# LCD_Cape.net
KiCad netlist of a schematic drawn in Altium Designer
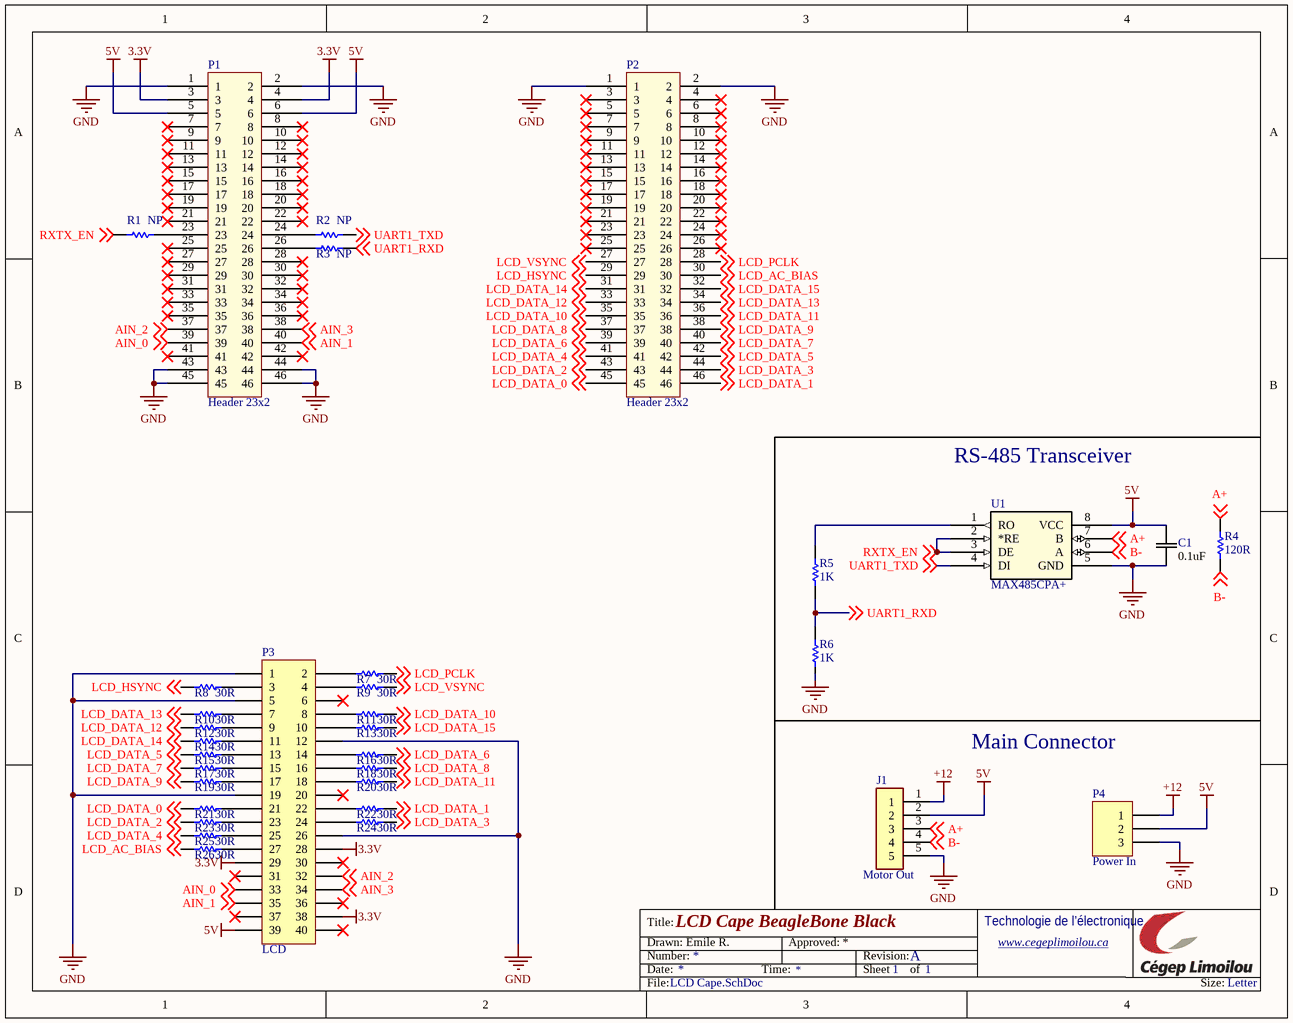
[diagram p0: LCD Cape.SchDoc]

(export (version "E")
  (design (tool "Eeschema 10.0.6"))
  (components
    (comp (ref "C1")
      (value "0.1uF")
      (footprint "0603")
      (description "Capacitor SMD 1206")
      (fields
        (field (name "MANUFACTURER_PART_NUMBER") "12065A820JAT2A")
        (field (name "Comment") "Capacitor 1206")
        (field (name "COPYRIGHT") "Copyright (C) 2018 Accelerated Designs. All rights reserved")
      )
      (libsource (lib "Schematic_Emile") (part "Capacitor 1206"))
    )
    (comp (ref "J1")
      (value "Motor Out")
      (footprint "JST 5POS 2.5mm 90°")
      (description "Connector")
      (fields (field (name "MANUFACTURER_PART_NUMBER") "S5B-XH-A-1(LF)(SN)"))
      (libsource (lib "Schematic_Emile") (part "JST 5POS"))
    )
    (comp (ref "P1") (value "Header 23x2") (libsource (lib "Schematic_Emile") (part "Header 23x2")))
    (comp (ref "P2") (value "Header 23x2") (libsource (lib "Schematic_Emile") (part "Header 23x2")))
    (comp (ref "P3")
      (value "LCD")
      (footprint "HDR2X20")
      (description "Header, 20-Pin, Dual row")
      (fields (field (name "PUBLISHER") "Altium Limited"))
      (libsource (lib "Miscellaneous Connectors") (part "Header 20X2"))
    )
    (comp (ref "P4")
      (value "Power In")
      (footprint "HDR1X3")
      (description "Header, 3-Pin")
      (fields (field (name "PUBLISHER") "Altium Limited"))
      (libsource (lib "Miscellaneous Connectors") (part "Header 3"))
    )
    (comp (ref "R1")
      (value "NP")
      (footprint "AXIAL-0.3")
      (description "Resistor")
      (fields (field (name "Comment") "Res1") (field (name "PUBLISHER") "Altium Limited"))
      (libsource (lib "Miscellaneous Devices") (part "Res1"))
    )
    (comp (ref "R2")
      (value "NP")
      (footprint "AXIAL-0.3")
      (description "Resistor")
      (fields (field (name "Comment") "Res1") (field (name "PUBLISHER") "Altium Limited"))
      (libsource (lib "Miscellaneous Devices") (part "Res1"))
    )
    (comp (ref "R3")
      (value "NP")
      (footprint "AXIAL-0.3")
      (description "Resistor")
      (fields (field (name "Comment") "Res1") (field (name "PUBLISHER") "Altium Limited"))
      (libsource (lib "Miscellaneous Devices") (part "Res1"))
    )
    (comp (ref "R4")
      (value "120R")
      (footprint "C1206")
      (description "Resistor")
      (fields (field (name "Comment") "Res1") (field (name "PUBLISHER") "Altium Limited"))
      (libsource (lib "Miscellaneous Devices") (part "Res1"))
    )
    (comp (ref "R5")
      (value "1K")
      (footprint "C1206")
      (description "Resistor")
      (fields (field (name "Comment") "Res1") (field (name "PUBLISHER") "Altium Limited"))
      (libsource (lib "Miscellaneous Devices") (part "Res1"))
    )
    (comp (ref "R6")
      (value "1K")
      (footprint "C1206")
      (description "Resistor")
      (fields (field (name "Comment") "Res1") (field (name "PUBLISHER") "Altium Limited"))
      (libsource (lib "Miscellaneous Devices") (part "Res1"))
    )
    (comp (ref "R7")
      (value "30R")
      (footprint "C1206")
      (description "Resistor")
      (fields (field (name "Comment") "Res1") (field (name "PUBLISHER") "Altium Limited"))
      (libsource (lib "Miscellaneous Devices") (part "Res1"))
    )
    (comp (ref "R8")
      (value "30R")
      (footprint "C1206")
      (description "Resistor")
      (fields (field (name "Comment") "Res1") (field (name "PUBLISHER") "Altium Limited"))
      (libsource (lib "Miscellaneous Devices") (part "Res1"))
    )
    (comp (ref "R9")
      (value "30R")
      (footprint "C1206")
      (description "Resistor")
      (fields (field (name "Comment") "Res1") (field (name "PUBLISHER") "Altium Limited"))
      (libsource (lib "Miscellaneous Devices") (part "Res1"))
    )
    (comp (ref "R10")
      (value "30R")
      (footprint "C1206")
      (description "Resistor")
      (fields (field (name "Comment") "Res1") (field (name "PUBLISHER") "Altium Limited"))
      (libsource (lib "Miscellaneous Devices") (part "Res1"))
    )
    (comp (ref "R11")
      (value "30R")
      (footprint "C1206")
      (description "Resistor")
      (fields (field (name "Comment") "Res1") (field (name "PUBLISHER") "Altium Limited"))
      (libsource (lib "Miscellaneous Devices") (part "Res1"))
    )
    (comp (ref "R12")
      (value "30R")
      (footprint "C1206")
      (description "Resistor")
      (fields (field (name "Comment") "Res1") (field (name "PUBLISHER") "Altium Limited"))
      (libsource (lib "Miscellaneous Devices") (part "Res1"))
    )
    (comp (ref "R13")
      (value "30R")
      (footprint "C1206")
      (description "Resistor")
      (fields (field (name "Comment") "Res1") (field (name "PUBLISHER") "Altium Limited"))
      (libsource (lib "Miscellaneous Devices") (part "Res1"))
    )
    (comp (ref "R14")
      (value "30R")
      (footprint "C1206")
      (description "Resistor")
      (fields (field (name "Comment") "Res1") (field (name "PUBLISHER") "Altium Limited"))
      (libsource (lib "Miscellaneous Devices") (part "Res1"))
    )
    (comp (ref "R15")
      (value "30R")
      (footprint "C1206")
      (description "Resistor")
      (fields (field (name "Comment") "Res1") (field (name "PUBLISHER") "Altium Limited"))
      (libsource (lib "Miscellaneous Devices") (part "Res1"))
    )
    (comp (ref "R16")
      (value "30R")
      (footprint "C1206")
      (description "Resistor")
      (fields (field (name "Comment") "Res1") (field (name "PUBLISHER") "Altium Limited"))
      (libsource (lib "Miscellaneous Devices") (part "Res1"))
    )
    (comp (ref "R17")
      (value "30R")
      (footprint "C1206")
      (description "Resistor")
      (fields (field (name "Comment") "Res1") (field (name "PUBLISHER") "Altium Limited"))
      (libsource (lib "Miscellaneous Devices") (part "Res1"))
    )
    (comp (ref "R18")
      (value "30R")
      (footprint "C1206")
      (description "Resistor")
      (fields (field (name "Comment") "Res1") (field (name "PUBLISHER") "Altium Limited"))
      (libsource (lib "Miscellaneous Devices") (part "Res1"))
    )
    (comp (ref "R19")
      (value "30R")
      (footprint "C1206")
      (description "Resistor")
      (fields (field (name "Comment") "Res1") (field (name "PUBLISHER") "Altium Limited"))
      (libsource (lib "Miscellaneous Devices") (part "Res1"))
    )
    (comp (ref "R20")
      (value "30R")
      (footprint "C1206")
      (description "Resistor")
      (fields (field (name "Comment") "Res1") (field (name "PUBLISHER") "Altium Limited"))
      (libsource (lib "Miscellaneous Devices") (part "Res1"))
    )
    (comp (ref "R21")
      (value "30R")
      (footprint "C1206")
      (description "Resistor")
      (fields (field (name "Comment") "Res1") (field (name "PUBLISHER") "Altium Limited"))
      (libsource (lib "Miscellaneous Devices") (part "Res1"))
    )
    (comp (ref "R22")
      (value "30R")
      (footprint "C1206")
      (description "Resistor")
      (fields (field (name "Comment") "Res1") (field (name "PUBLISHER") "Altium Limited"))
      (libsource (lib "Miscellaneous Devices") (part "Res1"))
    )
    (comp (ref "R23")
      (value "30R")
      (footprint "C1206")
      (description "Resistor")
      (fields (field (name "Comment") "Res1") (field (name "PUBLISHER") "Altium Limited"))
      (libsource (lib "Miscellaneous Devices") (part "Res1"))
    )
    (comp (ref "R24")
      (value "30R")
      (footprint "C1206")
      (description "Resistor")
      (fields (field (name "Comment") "Res1") (field (name "PUBLISHER") "Altium Limited"))
      (libsource (lib "Miscellaneous Devices") (part "Res1"))
    )
    (comp (ref "R25")
      (value "30R")
      (footprint "C1206")
      (description "Resistor")
      (fields (field (name "Comment") "Res1") (field (name "PUBLISHER") "Altium Limited"))
      (libsource (lib "Miscellaneous Devices") (part "Res1"))
    )
    (comp (ref "R26")
      (value "30R")
      (footprint "C1206")
      (description "Resistor")
      (fields (field (name "Comment") "Res1") (field (name "PUBLISHER") "Altium Limited"))
      (libsource (lib "Miscellaneous Devices") (part "Res1"))
    )
    (comp (ref "U1")
      (value "MAX485CPA+")
      (footprint "DIP 8 - 3D")
      (description "RS485 Communication")
      (fields (field (name "COPYRIGHT") "Copyright (C) 2018 Accelerated Designs. All rights reserved"))
      (libsource (lib "Schematic_Emile") (part "MAX485CPA+"))
    )
  )
  (nets
    (net (code "1") (name "+12") (class "Default")
      (node (ref "J1") (pin "1") (pinfunction "1_1") (pintype "passive"))
      (node (ref "P4") (pin "1") (pinfunction "1_1") (pintype "passive"))
    )
    (net (code "2") (name "3.3V") (class "Default")
      (node (ref "P1") (pin "3") (pinfunction "3_3") (pintype "passive"))
      (node (ref "P1") (pin "4") (pinfunction "4_4") (pintype "passive"))
      (node (ref "P3") (pin "28") (pinfunction "28_28") (pintype "passive"))
      (node (ref "P3") (pin "29") (pinfunction "29_29") (pintype "passive"))
      (node (ref "P3") (pin "38") (pinfunction "38_38") (pintype "passive"))
    )
    (net (code "3") (name "5V") (class "Default")
      (node (ref "C1") (pin "2") (pinfunction "2_2") (pintype "passive"))
      (node (ref "J1") (pin "2") (pinfunction "2_2") (pintype "passive"))
      (node (ref "P1") (pin "5") (pinfunction "5_5") (pintype "passive"))
      (node (ref "P1") (pin "6") (pinfunction "6_6") (pintype "passive"))
      (node (ref "P3") (pin "39") (pinfunction "39_39") (pintype "passive"))
      (node (ref "P4") (pin "2") (pinfunction "2_2") (pintype "passive"))
      (node (ref "U1") (pin "8") (pinfunction "VCC_8") (pintype "power_in"))
    )
    (net (code "4") (name "A+") (class "Default")
      (node (ref "J1") (pin "3") (pinfunction "3_3") (pintype "passive"))
      (node (ref "R4") (pin "1") (pinfunction "1_1") (pintype "passive"))
      (node (ref "U1") (pin "7") (pinfunction "B_7") (pintype "bidirectional"))
    )
    (net (code "5") (name "AIN_0") (class "Default")
      (node (ref "P1") (pin "39") (pinfunction "39_39") (pintype "passive"))
      (node (ref "P3") (pin "33") (pinfunction "33_33") (pintype "passive"))
    )
    (net (code "6") (name "AIN_1") (class "Default")
      (node (ref "P1") (pin "40") (pinfunction "40_40") (pintype "passive"))
      (node (ref "P3") (pin "35") (pinfunction "35_35") (pintype "passive"))
    )
    (net (code "7") (name "AIN_2") (class "Default")
      (node (ref "P1") (pin "37") (pinfunction "37_37") (pintype "passive"))
      (node (ref "P3") (pin "32") (pinfunction "32_32") (pintype "passive"))
    )
    (net (code "8") (name "AIN_3") (class "Default")
      (node (ref "P1") (pin "38") (pinfunction "38_38") (pintype "passive"))
      (node (ref "P3") (pin "34") (pinfunction "34_34") (pintype "passive"))
    )
    (net (code "9") (name "B-") (class "Default")
      (node (ref "J1") (pin "4") (pinfunction "4_4") (pintype "passive"))
      (node (ref "R4") (pin "2") (pinfunction "2_2") (pintype "passive"))
      (node (ref "U1") (pin "6") (pinfunction "A_6") (pintype "bidirectional"))
    )
    (net (code "10") (name "GND") (class "Default")
      (node (ref "C1") (pin "1") (pinfunction "1_1") (pintype "passive"))
      (node (ref "J1") (pin "5") (pinfunction "5_5") (pintype "passive"))
      (node (ref "P1") (pin "1") (pinfunction "1_1") (pintype "passive"))
      (node (ref "P1") (pin "2") (pinfunction "2_2") (pintype "passive"))
      (node (ref "P1") (pin "43") (pinfunction "43_43") (pintype "passive"))
      (node (ref "P1") (pin "44") (pinfunction "44_44") (pintype "passive"))
      (node (ref "P1") (pin "45") (pinfunction "45_45") (pintype "passive"))
      (node (ref "P1") (pin "46") (pinfunction "46_46") (pintype "passive"))
      (node (ref "P2") (pin "1") (pinfunction "1_1") (pintype "passive"))
      (node (ref "P2") (pin "2") (pinfunction "2_2") (pintype "passive"))
      (node (ref "P3") (pin "1") (pinfunction "1_1") (pintype "passive"))
      (node (ref "P3") (pin "12") (pinfunction "12_12") (pintype "passive"))
      (node (ref "P3") (pin "19") (pinfunction "19_19") (pintype "passive"))
      (node (ref "P3") (pin "26") (pinfunction "26_26") (pintype "passive"))
      (node (ref "P3") (pin "5") (pinfunction "5_5") (pintype "passive"))
      (node (ref "P4") (pin "3") (pinfunction "3_3") (pintype "passive"))
      (node (ref "R6") (pin "2") (pinfunction "2_2") (pintype "passive"))
      (node (ref "U1") (pin "5") (pinfunction "GND_5") (pintype "power_in"))
    )
    (net (code "11") (name "LCD_AC_BIAS") (class "Default")
      (node (ref "P2") (pin "30") (pinfunction "30_30") (pintype "passive"))
      (node (ref "R26") (pin "1") (pinfunction "1_1") (pintype "passive"))
    )
    (net (code "12") (name "LCD_DATA_0") (class "Default")
      (node (ref "P2") (pin "45") (pinfunction "45_45") (pintype "passive"))
      (node (ref "R21") (pin "1") (pinfunction "1_1") (pintype "passive"))
    )
    (net (code "13") (name "LCD_DATA_1") (class "Default")
      (node (ref "P2") (pin "46") (pinfunction "46_46") (pintype "passive"))
      (node (ref "R22") (pin "2") (pinfunction "2_2") (pintype "passive"))
    )
    (net (code "14") (name "LCD_DATA_2") (class "Default")
      (node (ref "P2") (pin "43") (pinfunction "43_43") (pintype "passive"))
      (node (ref "R23") (pin "1") (pinfunction "1_1") (pintype "passive"))
    )
    (net (code "15") (name "LCD_DATA_3") (class "Default")
      (node (ref "P2") (pin "44") (pinfunction "44_44") (pintype "passive"))
      (node (ref "R24") (pin "2") (pinfunction "2_2") (pintype "passive"))
    )
    (net (code "16") (name "LCD_DATA_4") (class "Default")
      (node (ref "P2") (pin "41") (pinfunction "41_41") (pintype "passive"))
      (node (ref "R25") (pin "1") (pinfunction "1_1") (pintype "passive"))
    )
    (net (code "17") (name "LCD_DATA_5") (class "Default")
      (node (ref "P2") (pin "42") (pinfunction "42_42") (pintype "passive"))
      (node (ref "R15") (pin "1") (pinfunction "1_1") (pintype "passive"))
    )
    (net (code "18") (name "LCD_DATA_6") (class "Default")
      (node (ref "P2") (pin "39") (pinfunction "39_39") (pintype "passive"))
      (node (ref "R16") (pin "2") (pinfunction "2_2") (pintype "passive"))
    )
    (net (code "19") (name "LCD_DATA_7") (class "Default")
      (node (ref "P2") (pin "40") (pinfunction "40_40") (pintype "passive"))
      (node (ref "R17") (pin "1") (pinfunction "1_1") (pintype "passive"))
    )
    (net (code "20") (name "LCD_DATA_8") (class "Default")
      (node (ref "P2") (pin "37") (pinfunction "37_37") (pintype "passive"))
      (node (ref "R18") (pin "2") (pinfunction "2_2") (pintype "passive"))
    )
    (net (code "21") (name "LCD_DATA_9") (class "Default")
      (node (ref "P2") (pin "38") (pinfunction "38_38") (pintype "passive"))
      (node (ref "R19") (pin "1") (pinfunction "1_1") (pintype "passive"))
    )
    (net (code "22") (name "LCD_DATA_10") (class "Default")
      (node (ref "P2") (pin "35") (pinfunction "35_35") (pintype "passive"))
      (node (ref "R11") (pin "2") (pinfunction "2_2") (pintype "passive"))
    )
    (net (code "23") (name "LCD_DATA_11") (class "Default")
      (node (ref "P2") (pin "36") (pinfunction "36_36") (pintype "passive"))
      (node (ref "R20") (pin "2") (pinfunction "2_2") (pintype "passive"))
    )
    (net (code "24") (name "LCD_DATA_12") (class "Default")
      (node (ref "P2") (pin "33") (pinfunction "33_33") (pintype "passive"))
      (node (ref "R12") (pin "1") (pinfunction "1_1") (pintype "passive"))
    )
    (net (code "25") (name "LCD_DATA_13") (class "Default")
      (node (ref "P2") (pin "34") (pinfunction "34_34") (pintype "passive"))
      (node (ref "R10") (pin "1") (pinfunction "1_1") (pintype "passive"))
    )
    (net (code "26") (name "LCD_DATA_14") (class "Default")
      (node (ref "P2") (pin "31") (pinfunction "31_31") (pintype "passive"))
      (node (ref "R14") (pin "1") (pinfunction "1_1") (pintype "passive"))
    )
    (net (code "27") (name "LCD_DATA_15") (class "Default")
      (node (ref "P2") (pin "32") (pinfunction "32_32") (pintype "passive"))
      (node (ref "R13") (pin "2") (pinfunction "2_2") (pintype "passive"))
    )
    (net (code "28") (name "LCD_HSYNC") (class "Default")
      (node (ref "P2") (pin "29") (pinfunction "29_29") (pintype "passive"))
      (node (ref "R8") (pin "1") (pinfunction "1_1") (pintype "passive"))
    )
    (net (code "29") (name "LCD_PCLK") (class "Default")
      (node (ref "P2") (pin "28") (pinfunction "28_28") (pintype "passive"))
      (node (ref "R7") (pin "2") (pinfunction "2_2") (pintype "passive"))
    )
    (net (code "30") (name "LCD_VSYNC") (class "Default")
      (node (ref "P2") (pin "27") (pinfunction "27_27") (pintype "passive"))
      (node (ref "R9") (pin "2") (pinfunction "2_2") (pintype "passive"))
    )
    (net (code "31") (name "Net-(P1-Pad23)") (class "Default")
      (node (ref "P1") (pin "23") (pinfunction "23_23") (pintype "passive"))
      (node (ref "R1") (pin "2") (pinfunction "2_2") (pintype "passive"))
    )
    (net (code "32") (name "Net-(P1-Pad24)") (class "Default")
      (node (ref "P1") (pin "24") (pinfunction "24_24") (pintype "passive"))
      (node (ref "R2") (pin "1") (pinfunction "1_1") (pintype "passive"))
    )
    (net (code "33") (name "Net-(P1-Pad26)") (class "Default")
      (node (ref "P1") (pin "26") (pinfunction "26_26") (pintype "passive"))
      (node (ref "R3") (pin "1") (pinfunction "1_1") (pintype "passive"))
    )
    (net (code "34") (name "Net-(P3-Pad2)") (class "Default")
      (node (ref "P3") (pin "2") (pinfunction "2_2") (pintype "passive"))
      (node (ref "R7") (pin "1") (pinfunction "1_1") (pintype "passive"))
    )
    (net (code "35") (name "Net-(P3-Pad3)") (class "Default")
      (node (ref "P3") (pin "3") (pinfunction "3_3") (pintype "passive"))
      (node (ref "R8") (pin "2") (pinfunction "2_2") (pintype "passive"))
    )
    (net (code "36") (name "Net-(P3-Pad4)") (class "Default")
      (node (ref "P3") (pin "4") (pinfunction "4_4") (pintype "passive"))
      (node (ref "R9") (pin "1") (pinfunction "1_1") (pintype "passive"))
    )
    (net (code "37") (name "Net-(P3-Pad7)") (class "Default")
      (node (ref "P3") (pin "7") (pinfunction "7_7") (pintype "passive"))
      (node (ref "R10") (pin "2") (pinfunction "2_2") (pintype "passive"))
    )
    (net (code "38") (name "Net-(P3-Pad8)") (class "Default")
      (node (ref "P3") (pin "8") (pinfunction "8_8") (pintype "passive"))
      (node (ref "R11") (pin "1") (pinfunction "1_1") (pintype "passive"))
    )
    (net (code "39") (name "Net-(P3-Pad9)") (class "Default")
      (node (ref "P3") (pin "9") (pinfunction "9_9") (pintype "passive"))
      (node (ref "R12") (pin "2") (pinfunction "2_2") (pintype "passive"))
    )
    (net (code "40") (name "Net-(P3-Pad10)") (class "Default")
      (node (ref "P3") (pin "10") (pinfunction "10_10") (pintype "passive"))
      (node (ref "R13") (pin "1") (pinfunction "1_1") (pintype "passive"))
    )
    (net (code "41") (name "Net-(P3-Pad11)") (class "Default")
      (node (ref "P3") (pin "11") (pinfunction "11_11") (pintype "passive"))
      (node (ref "R14") (pin "2") (pinfunction "2_2") (pintype "passive"))
    )
    (net (code "42") (name "Net-(P3-Pad13)") (class "Default")
      (node (ref "P3") (pin "13") (pinfunction "13_13") (pintype "passive"))
      (node (ref "R15") (pin "2") (pinfunction "2_2") (pintype "passive"))
    )
    (net (code "43") (name "Net-(P3-Pad14)") (class "Default")
      (node (ref "P3") (pin "14") (pinfunction "14_14") (pintype "passive"))
      (node (ref "R16") (pin "1") (pinfunction "1_1") (pintype "passive"))
    )
    (net (code "44") (name "Net-(P3-Pad15)") (class "Default")
      (node (ref "P3") (pin "15") (pinfunction "15_15") (pintype "passive"))
      (node (ref "R17") (pin "2") (pinfunction "2_2") (pintype "passive"))
    )
    (net (code "45") (name "Net-(P3-Pad16)") (class "Default")
      (node (ref "P3") (pin "16") (pinfunction "16_16") (pintype "passive"))
      (node (ref "R18") (pin "1") (pinfunction "1_1") (pintype "passive"))
    )
    (net (code "46") (name "Net-(P3-Pad17)") (class "Default")
      (node (ref "P3") (pin "17") (pinfunction "17_17") (pintype "passive"))
      (node (ref "R19") (pin "2") (pinfunction "2_2") (pintype "passive"))
    )
    (net (code "47") (name "Net-(P3-Pad18)") (class "Default")
      (node (ref "P3") (pin "18") (pinfunction "18_18") (pintype "passive"))
      (node (ref "R20") (pin "1") (pinfunction "1_1") (pintype "passive"))
    )
    (net (code "48") (name "Net-(P3-Pad21)") (class "Default")
      (node (ref "P3") (pin "21") (pinfunction "21_21") (pintype "passive"))
      (node (ref "R21") (pin "2") (pinfunction "2_2") (pintype "passive"))
    )
    (net (code "49") (name "Net-(P3-Pad22)") (class "Default")
      (node (ref "P3") (pin "22") (pinfunction "22_22") (pintype "passive"))
      (node (ref "R22") (pin "1") (pinfunction "1_1") (pintype "passive"))
    )
    (net (code "50") (name "Net-(P3-Pad23)") (class "Default")
      (node (ref "P3") (pin "23") (pinfunction "23_23") (pintype "passive"))
      (node (ref "R23") (pin "2") (pinfunction "2_2") (pintype "passive"))
    )
    (net (code "51") (name "Net-(P3-Pad24)") (class "Default")
      (node (ref "P3") (pin "24") (pinfunction "24_24") (pintype "passive"))
      (node (ref "R24") (pin "1") (pinfunction "1_1") (pintype "passive"))
    )
    (net (code "52") (name "Net-(P3-Pad25)") (class "Default")
      (node (ref "P3") (pin "25") (pinfunction "25_25") (pintype "passive"))
      (node (ref "R25") (pin "2") (pinfunction "2_2") (pintype "passive"))
    )
    (net (code "53") (name "Net-(P3-Pad27)") (class "Default")
      (node (ref "P3") (pin "27") (pinfunction "27_27") (pintype "passive"))
      (node (ref "R26") (pin "2") (pinfunction "2_2") (pintype "passive"))
    )
    (net (code "54") (name "Net-(U1-RO)") (class "Default")
      (node (ref "R5") (pin "1") (pinfunction "1_1") (pintype "passive"))
      (node (ref "U1") (pin "1") (pinfunction "RO_1") (pintype "output"))
    )
    (net (code "55") (name "RXTX_EN") (class "Default")
      (node (ref "R1") (pin "1") (pinfunction "1_1") (pintype "passive"))
      (node (ref "U1") (pin "2") (pinfunction "*RE_2") (pintype "input"))
      (node (ref "U1") (pin "3") (pinfunction "DE_3") (pintype "input"))
    )
    (net (code "56") (name "UART1_RXD") (class "Default")
      (node (ref "R3") (pin "2") (pinfunction "2_2") (pintype "passive"))
      (node (ref "R5") (pin "2") (pinfunction "2_2") (pintype "passive"))
      (node (ref "R6") (pin "1") (pinfunction "1_1") (pintype "passive"))
    )
    (net (code "57") (name "UART1_TXD") (class "Default")
      (node (ref "R2") (pin "2") (pinfunction "2_2") (pintype "passive"))
      (node (ref "U1") (pin "4") (pinfunction "DI_4") (pintype "input"))
    )
    (net (code "58") (name "unconnected-(P1-Pad7)") (class "Default")
      (node (ref "P1") (pin "7") (pinfunction "7_7") (pintype "passive+no_connect"))
    )
    (net (code "59") (name "unconnected-(P1-Pad8)") (class "Default")
      (node (ref "P1") (pin "8") (pinfunction "8_8") (pintype "passive+no_connect"))
    )
    (net (code "60") (name "unconnected-(P1-Pad9)") (class "Default")
      (node (ref "P1") (pin "9") (pinfunction "9_9") (pintype "passive+no_connect"))
    )
    (net (code "61") (name "unconnected-(P1-Pad10)") (class "Default")
      (node (ref "P1") (pin "10") (pinfunction "10_10") (pintype "passive+no_connect"))
    )
    (net (code "62") (name "unconnected-(P1-Pad11)") (class "Default")
      (node (ref "P1") (pin "11") (pinfunction "11_11") (pintype "passive+no_connect"))
    )
    (net (code "63") (name "unconnected-(P1-Pad12)") (class "Default")
      (node (ref "P1") (pin "12") (pinfunction "12_12") (pintype "passive+no_connect"))
    )
    (net (code "64") (name "unconnected-(P1-Pad13)") (class "Default")
      (node (ref "P1") (pin "13") (pinfunction "13_13") (pintype "passive+no_connect"))
    )
    (net (code "65") (name "unconnected-(P1-Pad14)") (class "Default")
      (node (ref "P1") (pin "14") (pinfunction "14_14") (pintype "passive+no_connect"))
    )
    (net (code "66") (name "unconnected-(P1-Pad15)") (class "Default")
      (node (ref "P1") (pin "15") (pinfunction "15_15") (pintype "passive+no_connect"))
    )
    (net (code "67") (name "unconnected-(P1-Pad16)") (class "Default")
      (node (ref "P1") (pin "16") (pinfunction "16_16") (pintype "passive+no_connect"))
    )
    (net (code "68") (name "unconnected-(P1-Pad17)") (class "Default")
      (node (ref "P1") (pin "17") (pinfunction "17_17") (pintype "passive+no_connect"))
    )
    (net (code "69") (name "unconnected-(P1-Pad18)") (class "Default")
      (node (ref "P1") (pin "18") (pinfunction "18_18") (pintype "passive+no_connect"))
    )
    (net (code "70") (name "unconnected-(P1-Pad19)") (class "Default")
      (node (ref "P1") (pin "19") (pinfunction "19_19") (pintype "passive+no_connect"))
    )
    (net (code "71") (name "unconnected-(P1-Pad20)") (class "Default")
      (node (ref "P1") (pin "20") (pinfunction "20_20") (pintype "passive+no_connect"))
    )
    (net (code "72") (name "unconnected-(P1-Pad21)") (class "Default")
      (node (ref "P1") (pin "21") (pinfunction "21_21") (pintype "passive+no_connect"))
    )
    (net (code "73") (name "unconnected-(P1-Pad22)") (class "Default")
      (node (ref "P1") (pin "22") (pinfunction "22_22") (pintype "passive+no_connect"))
    )
    (net (code "74") (name "unconnected-(P1-Pad25)") (class "Default")
      (node (ref "P1") (pin "25") (pinfunction "25_25") (pintype "passive+no_connect"))
    )
    (net (code "75") (name "unconnected-(P1-Pad27)") (class "Default")
      (node (ref "P1") (pin "27") (pinfunction "27_27") (pintype "passive+no_connect"))
    )
    (net (code "76") (name "unconnected-(P1-Pad28)") (class "Default")
      (node (ref "P1") (pin "28") (pinfunction "28_28") (pintype "passive+no_connect"))
    )
    (net (code "77") (name "unconnected-(P1-Pad29)") (class "Default")
      (node (ref "P1") (pin "29") (pinfunction "29_29") (pintype "passive+no_connect"))
    )
    (net (code "78") (name "unconnected-(P1-Pad30)") (class "Default")
      (node (ref "P1") (pin "30") (pinfunction "30_30") (pintype "passive+no_connect"))
    )
    (net (code "79") (name "unconnected-(P1-Pad31)") (class "Default")
      (node (ref "P1") (pin "31") (pinfunction "31_31") (pintype "passive+no_connect"))
    )
    (net (code "80") (name "unconnected-(P1-Pad32)") (class "Default")
      (node (ref "P1") (pin "32") (pinfunction "32_32") (pintype "passive+no_connect"))
    )
    (net (code "81") (name "unconnected-(P1-Pad33)") (class "Default")
      (node (ref "P1") (pin "33") (pinfunction "33_33") (pintype "passive+no_connect"))
    )
    (net (code "82") (name "unconnected-(P1-Pad34)") (class "Default")
      (node (ref "P1") (pin "34") (pinfunction "34_34") (pintype "passive+no_connect"))
    )
    (net (code "83") (name "unconnected-(P1-Pad35)") (class "Default")
      (node (ref "P1") (pin "35") (pinfunction "35_35") (pintype "passive+no_connect"))
    )
    (net (code "84") (name "unconnected-(P1-Pad36)") (class "Default")
      (node (ref "P1") (pin "36") (pinfunction "36_36") (pintype "passive+no_connect"))
    )
    (net (code "85") (name "unconnected-(P1-Pad41)") (class "Default")
      (node (ref "P1") (pin "41") (pinfunction "41_41") (pintype "passive+no_connect"))
    )
    (net (code "86") (name "unconnected-(P1-Pad42)") (class "Default")
      (node (ref "P1") (pin "42") (pinfunction "42_42") (pintype "passive+no_connect"))
    )
    (net (code "87") (name "unconnected-(P2-Pad3)") (class "Default")
      (node (ref "P2") (pin "3") (pinfunction "3_3") (pintype "passive+no_connect"))
    )
    (net (code "88") (name "unconnected-(P2-Pad4)") (class "Default")
      (node (ref "P2") (pin "4") (pinfunction "4_4") (pintype "passive+no_connect"))
    )
    (net (code "89") (name "unconnected-(P2-Pad5)") (class "Default")
      (node (ref "P2") (pin "5") (pinfunction "5_5") (pintype "passive+no_connect"))
    )
    (net (code "90") (name "unconnected-(P2-Pad6)") (class "Default")
      (node (ref "P2") (pin "6") (pinfunction "6_6") (pintype "passive+no_connect"))
    )
    (net (code "91") (name "unconnected-(P2-Pad7)") (class "Default")
      (node (ref "P2") (pin "7") (pinfunction "7_7") (pintype "passive+no_connect"))
    )
    (net (code "92") (name "unconnected-(P2-Pad8)") (class "Default")
      (node (ref "P2") (pin "8") (pinfunction "8_8") (pintype "passive+no_connect"))
    )
    (net (code "93") (name "unconnected-(P2-Pad9)") (class "Default")
      (node (ref "P2") (pin "9") (pinfunction "9_9") (pintype "passive+no_connect"))
    )
    (net (code "94") (name "unconnected-(P2-Pad10)") (class "Default")
      (node (ref "P2") (pin "10") (pinfunction "10_10") (pintype "passive+no_connect"))
    )
    (net (code "95") (name "unconnected-(P2-Pad11)") (class "Default")
      (node (ref "P2") (pin "11") (pinfunction "11_11") (pintype "passive+no_connect"))
    )
    (net (code "96") (name "unconnected-(P2-Pad12)") (class "Default")
      (node (ref "P2") (pin "12") (pinfunction "12_12") (pintype "passive+no_connect"))
    )
    (net (code "97") (name "unconnected-(P2-Pad13)") (class "Default")
      (node (ref "P2") (pin "13") (pinfunction "13_13") (pintype "passive+no_connect"))
    )
    (net (code "98") (name "unconnected-(P2-Pad14)") (class "Default")
      (node (ref "P2") (pin "14") (pinfunction "14_14") (pintype "passive+no_connect"))
    )
    (net (code "99") (name "unconnected-(P2-Pad15)") (class "Default")
      (node (ref "P2") (pin "15") (pinfunction "15_15") (pintype "passive+no_connect"))
    )
    (net (code "100") (name "unconnected-(P2-Pad16)") (class "Default")
      (node (ref "P2") (pin "16") (pinfunction "16_16") (pintype "passive+no_connect"))
    )
    (net (code "101") (name "unconnected-(P2-Pad17)") (class "Default")
      (node (ref "P2") (pin "17") (pinfunction "17_17") (pintype "passive+no_connect"))
    )
    (net (code "102") (name "unconnected-(P2-Pad18)") (class "Default")
      (node (ref "P2") (pin "18") (pinfunction "18_18") (pintype "passive+no_connect"))
    )
    (net (code "103") (name "unconnected-(P2-Pad19)") (class "Default")
      (node (ref "P2") (pin "19") (pinfunction "19_19") (pintype "passive+no_connect"))
    )
    (net (code "104") (name "unconnected-(P2-Pad20)") (class "Default")
      (node (ref "P2") (pin "20") (pinfunction "20_20") (pintype "passive+no_connect"))
    )
    (net (code "105") (name "unconnected-(P2-Pad21)") (class "Default")
      (node (ref "P2") (pin "21") (pinfunction "21_21") (pintype "passive+no_connect"))
    )
    (net (code "106") (name "unconnected-(P2-Pad22)") (class "Default")
      (node (ref "P2") (pin "22") (pinfunction "22_22") (pintype "passive+no_connect"))
    )
    (net (code "107") (name "unconnected-(P2-Pad23)") (class "Default")
      (node (ref "P2") (pin "23") (pinfunction "23_23") (pintype "passive+no_connect"))
    )
    (net (code "108") (name "unconnected-(P2-Pad24)") (class "Default")
      (node (ref "P2") (pin "24") (pinfunction "24_24") (pintype "passive+no_connect"))
    )
    (net (code "109") (name "unconnected-(P2-Pad25)") (class "Default")
      (node (ref "P2") (pin "25") (pinfunction "25_25") (pintype "passive+no_connect"))
    )
    (net (code "110") (name "unconnected-(P2-Pad26)") (class "Default")
      (node (ref "P2") (pin "26") (pinfunction "26_26") (pintype "passive+no_connect"))
    )
    (net (code "111") (name "unconnected-(P3-Pad6)") (class "Default")
      (node (ref "P3") (pin "6") (pinfunction "6_6") (pintype "passive+no_connect"))
    )
    (net (code "112") (name "unconnected-(P3-Pad20)") (class "Default")
      (node (ref "P3") (pin "20") (pinfunction "20_20") (pintype "passive+no_connect"))
    )
    (net (code "113") (name "unconnected-(P3-Pad30)") (class "Default")
      (node (ref "P3") (pin "30") (pinfunction "30_30") (pintype "passive+no_connect"))
    )
    (net (code "114") (name "unconnected-(P3-Pad31)") (class "Default")
      (node (ref "P3") (pin "31") (pinfunction "31_31") (pintype "passive+no_connect"))
    )
    (net (code "115") (name "unconnected-(P3-Pad36)") (class "Default")
      (node (ref "P3") (pin "36") (pinfunction "36_36") (pintype "passive+no_connect"))
    )
    (net (code "116") (name "unconnected-(P3-Pad37)") (class "Default")
      (node (ref "P3") (pin "37") (pinfunction "37_37") (pintype "passive+no_connect"))
    )
    (net (code "117") (name "unconnected-(P3-Pad40)") (class "Default")
      (node (ref "P3") (pin "40") (pinfunction "40_40") (pintype "passive+no_connect"))
    )
  )
)
